# UI_BOARD.net
KiCad netlist of a schematic drawn in EAGLE
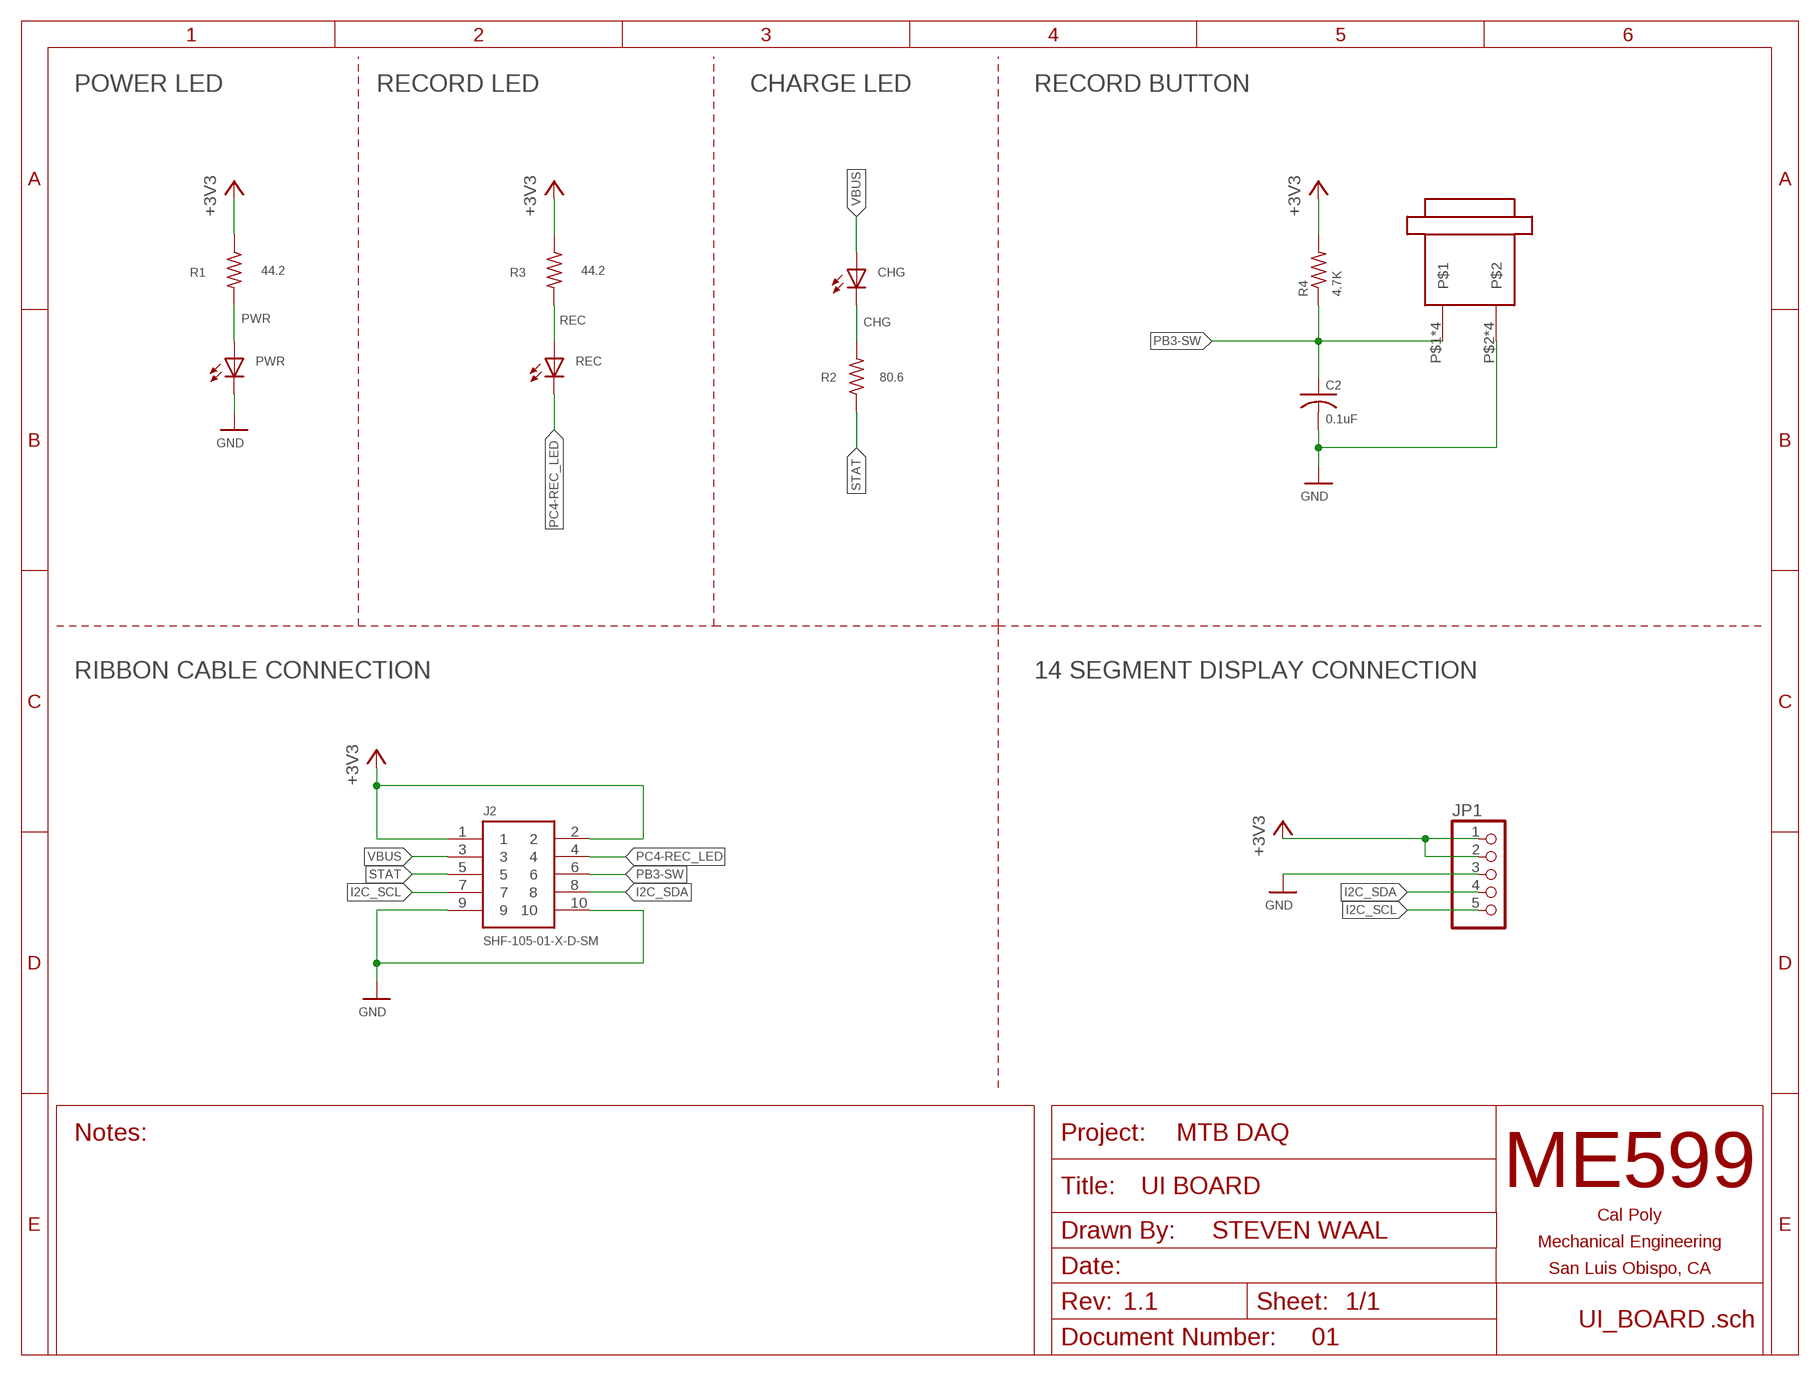
[diagram p0: schematic, sheet 1]

(export (version "E")
  (design (tool "Eeschema 10.0.6"))
  (components
    (comp (ref "C2")
      (value "0.1uF")
      (footprint "eagle-import:C0805")
      (libsource (lib "eagle-import") (part "C-USC0805"))
    )
    (comp (ref "CHG")
      (value "PANEL_MOUNT_LED")
      (footprint "eagle-import:PANEL_MOUNT_LED")
      (libsource (lib "eagle-import") (part "PANEL_MOUNT_LED"))
    )
    (comp (ref "J2")
      (value "SHF-105-01-X-D-SM")
      (footprint "eagle-import:SHF-105-01-X-D-SM")
      (fields (field (name "MF") "Samtec") (field (name "MP") "SHF-105-01-L-D-SM"))
      (libsource (lib "eagle-import") (part "SHF-105-01-X-D-SM"))
    )
    (comp (ref "JP1")
      (value "PINHD-1X5")
      (footprint "eagle-import:1X05")
      (libsource (lib "eagle-import") (part "PINHD-1X5"))
    )
    (comp (ref "PWR")
      (value "PANEL_MOUNT_LED")
      (footprint "eagle-import:PANEL_MOUNT_LED")
      (libsource (lib "eagle-import") (part "PANEL_MOUNT_LED"))
    )
    (comp (ref "R1")
      (value "44.2")
      (footprint "eagle-import:R0805")
      (libsource (lib "eagle-import") (part "R-US_R0805"))
    )
    (comp (ref "R2")
      (value "80.6")
      (footprint "eagle-import:R0805")
      (libsource (lib "eagle-import") (part "R-US_R0805"))
    )
    (comp (ref "R3")
      (value "44.2")
      (footprint "eagle-import:R0805")
      (libsource (lib "eagle-import") (part "R-US_R0805"))
    )
    (comp (ref "R4")
      (value "4.7K")
      (footprint "eagle-import:R0805")
      (libsource (lib "eagle-import") (part "R-US_R0805"))
    )
    (comp (ref "REC")
      (value "PANEL_MOUNT_LED")
      (footprint "eagle-import:PANEL_MOUNT_LED")
      (libsource (lib "eagle-import") (part "PANEL_MOUNT_LED"))
    )
    (comp (ref "U$4")
      (value "PANEL_MOUNT_PUSH_BUTTON")
      (footprint "eagle-import:PANEL_MOUNT_PUSH_BUTTON")
      (libsource (lib "eagle-import") (part "PANEL_MOUNT_PUSH_BUTTON"))
    )
  )
  (nets
    (net (code "1") (name "+3V3") (class "Default")
      (node (ref "J2") (pin "1") (pinfunction "1_1") (pintype "bidirectional"))
      (node (ref "J2") (pin "2") (pinfunction "2_2") (pintype "bidirectional"))
      (node (ref "JP1") (pin "1") (pinfunction "1_1") (pintype "passive"))
      (node (ref "JP1") (pin "2") (pinfunction "2_2") (pintype "passive"))
      (node (ref "R1") (pin "1") (pinfunction "1_1") (pintype "passive"))
      (node (ref "R3") (pin "1") (pinfunction "1_1") (pintype "passive"))
      (node (ref "R4") (pin "2") (pinfunction "2_2") (pintype "passive"))
    )
    (net (code "2") (name "/CHG") (class "Default")
      (node (ref "CHG") (pin "P$2") (pinfunction "2_P$2") (pintype "passive"))
      (node (ref "R2") (pin "2") (pinfunction "2_2") (pintype "passive"))
    )
    (net (code "3") (name "/PWR") (class "Default")
      (node (ref "PWR") (pin "P$1") (pinfunction "1_P$1") (pintype "passive"))
      (node (ref "R1") (pin "2") (pinfunction "2_2") (pintype "passive"))
    )
    (net (code "4") (name "/REC") (class "Default")
      (node (ref "R3") (pin "2") (pinfunction "2_2") (pintype "passive"))
      (node (ref "REC") (pin "P$1") (pinfunction "1_P$1") (pintype "passive"))
    )
    (net (code "5") (name "GND") (class "Default")
      (node (ref "C2") (pin "2") (pinfunction "2_2") (pintype "passive"))
      (node (ref "J2") (pin "10") (pinfunction "10_10") (pintype "bidirectional"))
      (node (ref "J2") (pin "9") (pinfunction "9_9") (pintype "bidirectional"))
      (node (ref "JP1") (pin "3") (pinfunction "3_3") (pintype "passive"))
      (node (ref "PWR") (pin "P$2") (pinfunction "2_P$2") (pintype "passive"))
      (node (ref "U$4") (pin "P$2") (pinfunction "P$2_P$2") (pintype "bidirectional"))
      (node (ref "U$4") (pin "P$4") (pinfunction "P$2_P$4") (pintype "bidirectional"))
      (node (ref "U$4") (pin "P$6") (pinfunction "P$2_P$6") (pintype "bidirectional"))
      (node (ref "U$4") (pin "P$8") (pinfunction "P$2_P$8") (pintype "bidirectional"))
    )
    (net (code "6") (name "I2C_SCL") (class "Default")
      (node (ref "J2") (pin "7") (pinfunction "7_7") (pintype "bidirectional"))
      (node (ref "JP1") (pin "5") (pinfunction "5_5") (pintype "passive"))
    )
    (net (code "7") (name "I2C_SDA") (class "Default")
      (node (ref "J2") (pin "8") (pinfunction "8_8") (pintype "bidirectional"))
      (node (ref "JP1") (pin "4") (pinfunction "4_4") (pintype "passive"))
    )
    (net (code "8") (name "PB3-SW") (class "Default")
      (node (ref "C2") (pin "1") (pinfunction "1_1") (pintype "passive"))
      (node (ref "J2") (pin "6") (pinfunction "6_6") (pintype "bidirectional"))
      (node (ref "R4") (pin "1") (pinfunction "1_1") (pintype "passive"))
      (node (ref "U$4") (pin "P$1") (pinfunction "P$1_P$1") (pintype "bidirectional"))
      (node (ref "U$4") (pin "P$3") (pinfunction "P$1_P$3") (pintype "bidirectional"))
      (node (ref "U$4") (pin "P$5") (pinfunction "P$1_P$5") (pintype "bidirectional"))
      (node (ref "U$4") (pin "P$7") (pinfunction "P$1_P$7") (pintype "bidirectional"))
    )
    (net (code "9") (name "PC4-REC_LED") (class "Default")
      (node (ref "J2") (pin "4") (pinfunction "4_4") (pintype "bidirectional"))
      (node (ref "REC") (pin "P$2") (pinfunction "2_P$2") (pintype "passive"))
    )
    (net (code "10") (name "STAT") (class "Default")
      (node (ref "J2") (pin "5") (pinfunction "5_5") (pintype "bidirectional"))
      (node (ref "R2") (pin "1") (pinfunction "1_1") (pintype "passive"))
    )
    (net (code "11") (name "VBUS") (class "Default")
      (node (ref "CHG") (pin "P$1") (pinfunction "1_P$1") (pintype "passive"))
      (node (ref "J2") (pin "3") (pinfunction "3_3") (pintype "bidirectional"))
    )
  )
)
